# VoltageSourcePCBV3LT1494.net
KiCad netlist of a schematic drawn in EAGLE
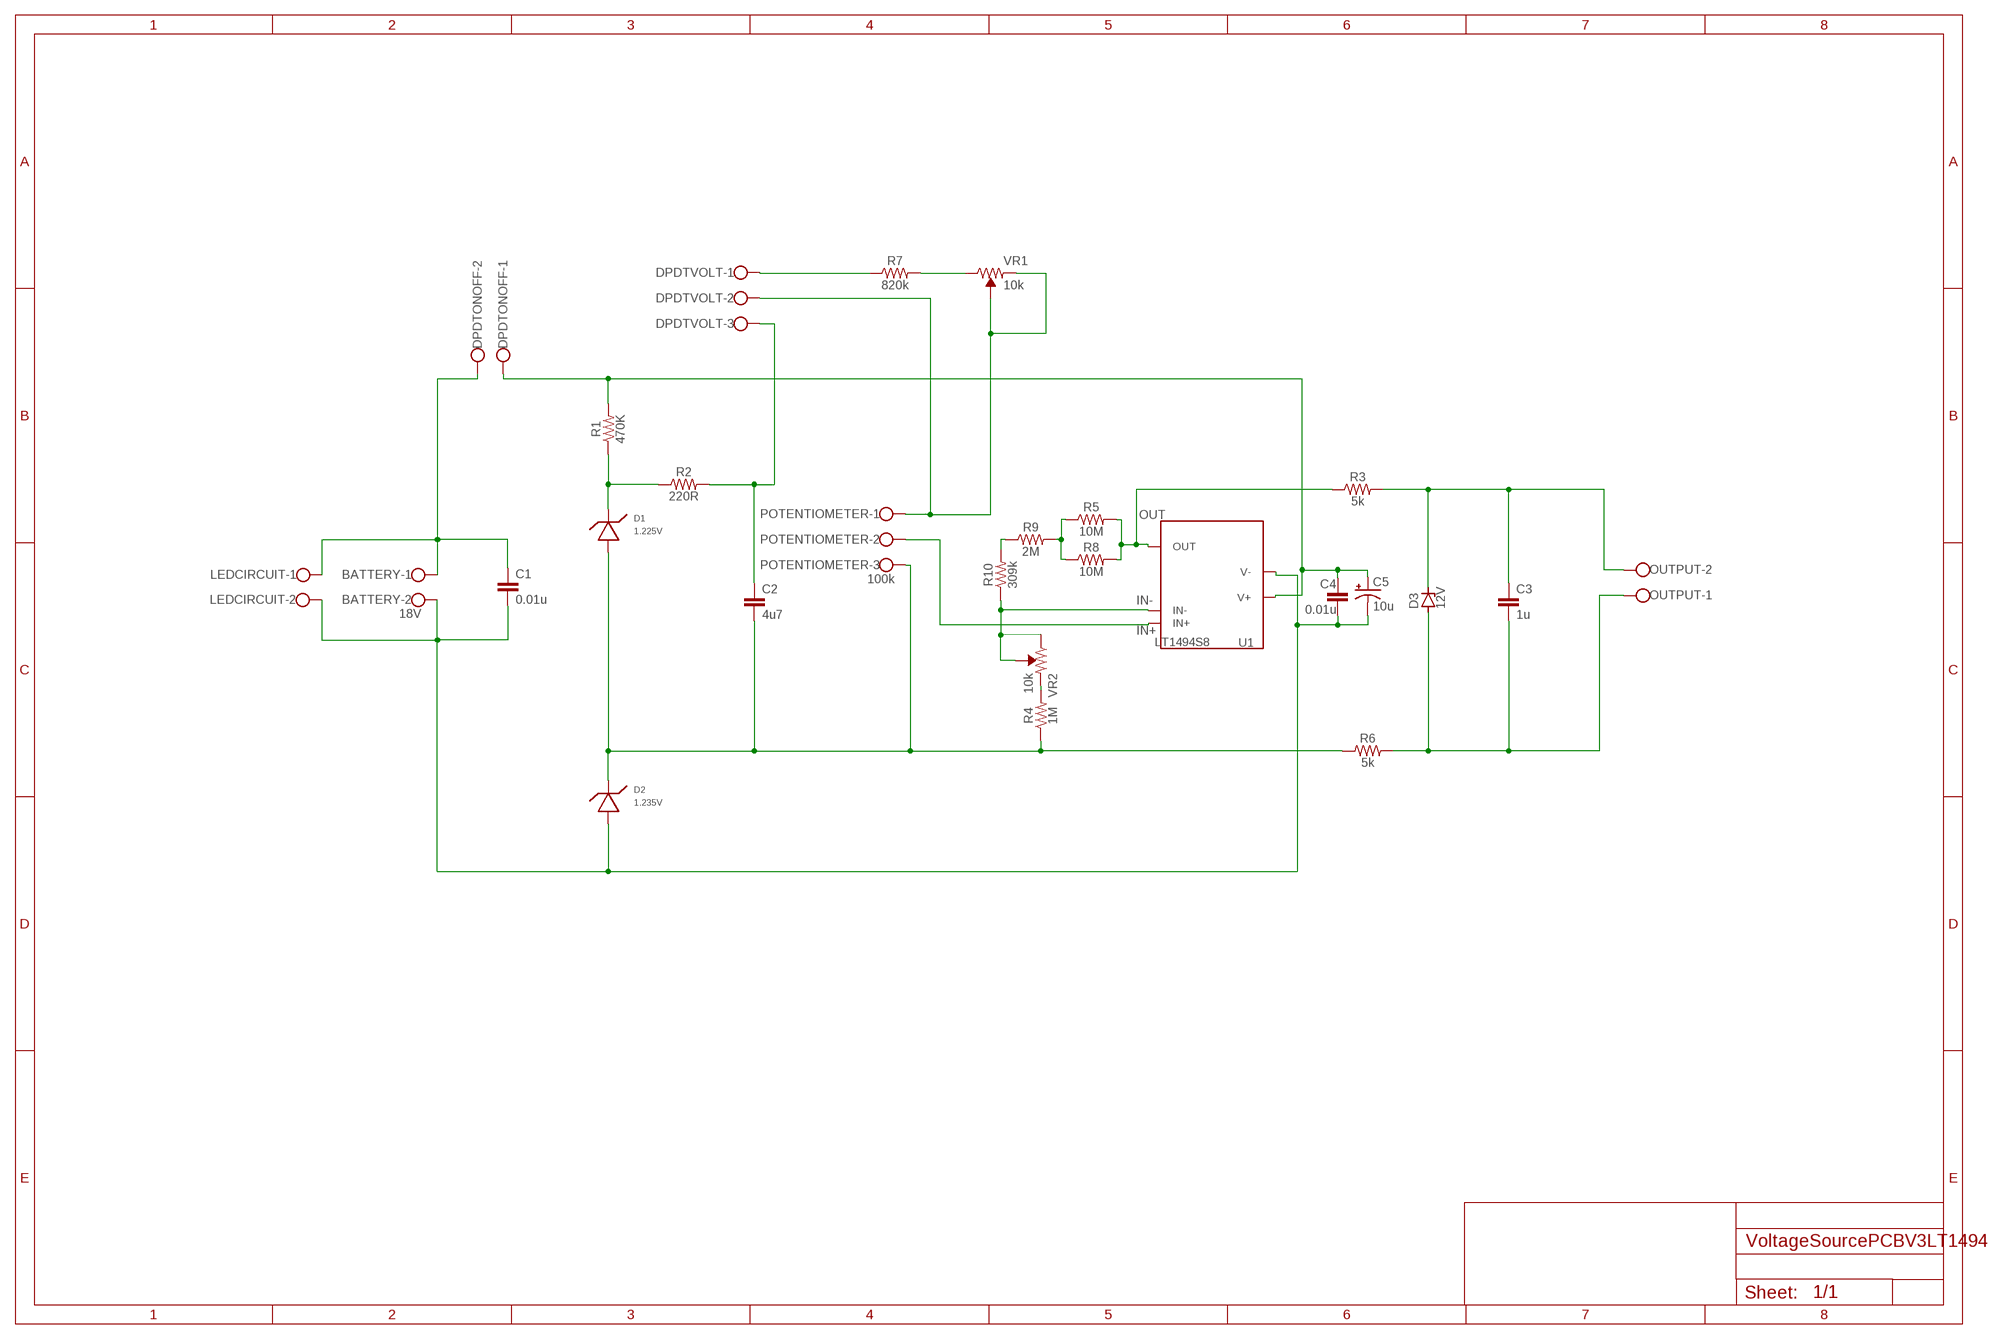
[diagram p0: schematic, sheet 1]

(export (version "E")
  (design (tool "Eeschema 10.0.6"))
  (components
    (comp (ref "BATTERY")
      (value "18V")
      (footprint "eagle-import:W237-102")
      (fields (field (name "MPN") "237-102"))
      (libsource (lib "eagle-import") (part "W237-102"))
    )
    (comp (ref "C1")
      (value "0.01u")
      (footprint "eagle-import:0805")
      (libsource (lib "eagle-import") (part "0.33UF/330NF-0805-50V-10%"))
    )
    (comp (ref "C2")
      (value "4u7")
      (footprint "eagle-import:0805")
      (libsource (lib "eagle-import") (part "0.33UF/330NF-0805-50V-10%"))
    )
    (comp (ref "C3")
      (value "1u")
      (footprint "eagle-import:0805")
      (libsource (lib "eagle-import") (part "0.33UF/330NF-0805-50V-10%"))
    )
    (comp (ref "C4")
      (value "0.01u")
      (footprint "eagle-import:0805")
      (libsource (lib "eagle-import") (part "0.33UF/330NF-0805-50V-10%"))
    )
    (comp (ref "C5")
      (value "10u")
      (footprint "eagle-import:EIA7343")
      (libsource (lib "eagle-import") (part "100UF-POLAR-EIA7343-10V-10%(TANT)"))
    )
    (comp (ref "D1")
      (value "1.225V")
      (footprint "eagle-import:S8PACKAGE")
      (libsource (lib "eagle-import") (part "LT1004CS8SMD"))
    )
    (comp (ref "D2")
      (value "1.235V")
      (footprint "eagle-import:SOIC-8PACKAGE")
      (libsource (lib "eagle-import") (part "LM385BDSMD"))
    )
    (comp (ref "D3")
      (value "12V")
      (footprint "eagle-import:SOT23")
      (libsource (lib "eagle-import") (part "ZENER-DIODESOT23"))
    )
    (comp (ref "DPDTONOFF")
      (value "W237-102")
      (footprint "eagle-import:W237-102")
      (fields (field (name "MPN") "237-102"))
      (libsource (lib "eagle-import") (part "W237-102"))
    )
    (comp (ref "DPDTVOLT")
      (value "W237-103")
      (footprint "eagle-import:W237-103")
      (fields (field (name "MPN") "237-103"))
      (libsource (lib "eagle-import") (part "W237-103"))
    )
    (comp (ref "LEDCIRCUIT")
      (value "W237-102")
      (footprint "eagle-import:W237-102")
      (fields (field (name "MPN") "237-102"))
      (libsource (lib "eagle-import") (part "W237-102"))
    )
    (comp (ref "OUTPUT")
      (value "W237-102")
      (footprint "eagle-import:W237-102")
      (fields (field (name "MPN") "237-102"))
      (libsource (lib "eagle-import") (part "W237-102"))
    )
    (comp (ref "POTENTIOMETER")
      (value "100k")
      (footprint "eagle-import:W237-103")
      (fields (field (name "MPN") "237-103"))
      (libsource (lib "eagle-import") (part "W237-103"))
    )
    (comp (ref "R1")
      (value "470K")
      (footprint "eagle-import:0805")
      (libsource (lib "eagle-import") (part "RESISTOR0805"))
    )
    (comp (ref "R2")
      (value "220R")
      (footprint "eagle-import:0805")
      (libsource (lib "eagle-import") (part "RESISTOR0805"))
    )
    (comp (ref "R3")
      (value "5k")
      (footprint "eagle-import:0805")
      (libsource (lib "eagle-import") (part "RESISTOR0805"))
    )
    (comp (ref "R4")
      (value "1M")
      (footprint "eagle-import:0805")
      (libsource (lib "eagle-import") (part "RESISTOR0805"))
    )
    (comp (ref "R5")
      (value "10M")
      (footprint "eagle-import:0805")
      (libsource (lib "eagle-import") (part "RESISTOR0805"))
    )
    (comp (ref "R6")
      (value "5k")
      (footprint "eagle-import:0805")
      (libsource (lib "eagle-import") (part "RESISTOR0805"))
    )
    (comp (ref "R7")
      (value "820k")
      (footprint "eagle-import:0805")
      (libsource (lib "eagle-import") (part "RESISTOR0805"))
    )
    (comp (ref "R8")
      (value "10M")
      (footprint "eagle-import:0805")
      (libsource (lib "eagle-import") (part "RESISTOR0805"))
    )
    (comp (ref "R9")
      (value "2M")
      (footprint "eagle-import:0805")
      (libsource (lib "eagle-import") (part "RESISTOR0805"))
    )
    (comp (ref "R10")
      (value "309k")
      (footprint "eagle-import:0805")
      (libsource (lib "eagle-import") (part "RESISTOR0805"))
    )
    (comp (ref "U1")
      (value "LT1494S8")
      (footprint "eagle-import:S8PACKAGE")
      (libsource (lib "eagle-import") (part "LT1494S8"))
    )
    (comp (ref "VR1")
      (value "10k")
      (footprint "eagle-import:TRIMPOT-SMD-TC33X")
      (libsource (lib "eagle-import") (part "TRIMPOT-SMD-3MM-OPEN-1/10W-25%"))
    )
    (comp (ref "VR2")
      (value "10k")
      (footprint "eagle-import:TRIMPOT-SMD-TC33X")
      (libsource (lib "eagle-import") (part "TRIMPOT-SMD-3MM-OPEN-1/10W-25%"))
    )
  )
  (nets
    (net (code "1") (name "/IN+") (class "Default")
      (node (ref "POTENTIOMETER") (pin "2") (pinfunction "KL_2") (pintype "passive"))
      (node (ref "U1") (pin "3") (pinfunction "IN+_3") (pintype "input"))
    )
    (net (code "2") (name "/IN-") (class "Default")
      (node (ref "R10") (pin "1") (pinfunction "1_1") (pintype "passive"))
      (node (ref "U1") (pin "2") (pinfunction "IN-_2") (pintype "input"))
      (node (ref "VR2") (pin "1") (pinfunction "CW_1") (pintype "passive"))
      (node (ref "VR2") (pin "2") (pinfunction "WIPER_2") (pintype "passive"))
    )
    (net (code "3") (name "/OUT") (class "Default")
      (node (ref "R3") (pin "1") (pinfunction "1_1") (pintype "passive"))
      (node (ref "R5") (pin "2") (pinfunction "2_2") (pintype "passive"))
      (node (ref "R8") (pin "2") (pinfunction "2_2") (pintype "passive"))
      (node (ref "U1") (pin "6") (pinfunction "OUT_6") (pintype "output"))
    )
    (net (code "4") (name "Net-(BATTERYA-KL)") (class "Default")
      (node (ref "BATTERY") (pin "1") (pinfunction "KL_1") (pintype "passive"))
      (node (ref "C1") (pin "1") (pinfunction "1_1") (pintype "passive"))
      (node (ref "DPDTONOFF") (pin "2") (pinfunction "KL_2") (pintype "passive"))
      (node (ref "LEDCIRCUIT") (pin "1") (pinfunction "KL_1") (pintype "passive"))
    )
    (net (code "5") (name "Net-(BATTERYB-KL)") (class "Default")
      (node (ref "BATTERY") (pin "2") (pinfunction "KL_2") (pintype "passive"))
      (node (ref "C1") (pin "2") (pinfunction "2_2") (pintype "passive"))
      (node (ref "C4") (pin "2") (pinfunction "2_2") (pintype "passive"))
      (node (ref "C5") (pin "C") (pinfunction "-_C") (pintype "passive"))
      (node (ref "D2") (pin "4") (pinfunction "ANODE_4") (pintype "bidirectional"))
      (node (ref "LEDCIRCUIT") (pin "2") (pinfunction "KL_2") (pintype "passive"))
      (node (ref "U1") (pin "4") (pinfunction "V-_4") (pintype "power_in"))
    )
    (net (code "6") (name "Net-(C5-+)") (class "Default")
      (node (ref "C4") (pin "1") (pinfunction "1_1") (pintype "passive"))
      (node (ref "C5") (pin "A") (pinfunction "+_A") (pintype "passive"))
      (node (ref "DPDTONOFF") (pin "1") (pinfunction "KL_1") (pintype "passive"))
      (node (ref "R1") (pin "2") (pinfunction "2_2") (pintype "passive"))
      (node (ref "U1") (pin "7") (pinfunction "V+_7") (pintype "power_in"))
    )
    (net (code "7") (name "Net-(D1-ANODE)") (class "Default")
      (node (ref "C2") (pin "2") (pinfunction "2_2") (pintype "passive"))
      (node (ref "D1") (pin "4") (pinfunction "ANODE_4") (pintype "bidirectional"))
      (node (ref "D2") (pin "8") (pinfunction "CATHODE_8") (pintype "bidirectional"))
      (node (ref "POTENTIOMETER") (pin "3") (pinfunction "KL_3") (pintype "passive"))
      (node (ref "R4") (pin "1") (pinfunction "1_1") (pintype "passive"))
      (node (ref "R6") (pin "1") (pinfunction "1_1") (pintype "passive"))
    )
    (net (code "8") (name "Net-(D1-CATHODE-Pad6)") (class "Default")
      (node (ref "D1") (pin "6") (pinfunction "CATHODE_6") (pintype "bidirectional"))
      (node (ref "D1") (pin "8") (pinfunction "CATHODE_8") (pintype "bidirectional"))
      (node (ref "R1") (pin "1") (pinfunction "1_1") (pintype "passive"))
      (node (ref "R2") (pin "1") (pinfunction "1_1") (pintype "passive"))
    )
    (net (code "9") (name "Net-(D3-A)") (class "Default")
      (node (ref "C3") (pin "2") (pinfunction "2_2") (pintype "passive"))
      (node (ref "D3") (pin "1") (pinfunction "A_1") (pintype "passive"))
      (node (ref "OUTPUT") (pin "1") (pinfunction "KL_1") (pintype "passive"))
      (node (ref "R6") (pin "2") (pinfunction "2_2") (pintype "passive"))
    )
    (net (code "10") (name "Net-(D3-C)") (class "Default")
      (node (ref "C3") (pin "1") (pinfunction "1_1") (pintype "passive"))
      (node (ref "D3") (pin "3") (pinfunction "C_3") (pintype "passive"))
      (node (ref "OUTPUT") (pin "2") (pinfunction "KL_2") (pintype "passive"))
      (node (ref "R3") (pin "2") (pinfunction "2_2") (pintype "passive"))
    )
    (net (code "11") (name "Net-(DPDTVOLTA-KL)") (class "Default")
      (node (ref "DPDTVOLT") (pin "1") (pinfunction "KL_1") (pintype "passive"))
      (node (ref "R7") (pin "1") (pinfunction "1_1") (pintype "passive"))
    )
    (net (code "12") (name "Net-(DPDTVOLTB-KL)") (class "Default")
      (node (ref "DPDTVOLT") (pin "2") (pinfunction "KL_2") (pintype "passive"))
      (node (ref "POTENTIOMETER") (pin "1") (pinfunction "KL_1") (pintype "passive"))
      (node (ref "VR1") (pin "2") (pinfunction "WIPER_2") (pintype "passive"))
      (node (ref "VR1") (pin "3") (pinfunction "CCW_3") (pintype "passive"))
    )
    (net (code "13") (name "Net-(DPDTVOLTC-KL)") (class "Default")
      (node (ref "C2") (pin "1") (pinfunction "1_1") (pintype "passive"))
      (node (ref "DPDTVOLT") (pin "3") (pinfunction "KL_3") (pintype "passive"))
      (node (ref "R2") (pin "2") (pinfunction "2_2") (pintype "passive"))
    )
    (net (code "14") (name "Net-(R5-Pad1)") (class "Default")
      (node (ref "R5") (pin "1") (pinfunction "1_1") (pintype "passive"))
      (node (ref "R8") (pin "1") (pinfunction "1_1") (pintype "passive"))
      (node (ref "R9") (pin "2") (pinfunction "2_2") (pintype "passive"))
    )
    (net (code "15") (name "Net-(R10-Pad2)") (class "Default")
      (node (ref "R10") (pin "2") (pinfunction "2_2") (pintype "passive"))
      (node (ref "R9") (pin "1") (pinfunction "1_1") (pintype "passive"))
    )
    (net (code "16") (name "Net-(VR1-CW)") (class "Default")
      (node (ref "R7") (pin "2") (pinfunction "2_2") (pintype "passive"))
      (node (ref "VR1") (pin "1") (pinfunction "CW_1") (pintype "passive"))
    )
    (net (code "17") (name "Net-(VR2-CCW)") (class "Default")
      (node (ref "R4") (pin "2") (pinfunction "2_2") (pintype "passive"))
      (node (ref "VR2") (pin "3") (pinfunction "CCW_3") (pintype "passive"))
    )
  )
)
